# CCD.net
KiCad netlist of a schematic drawn in Altium Designer
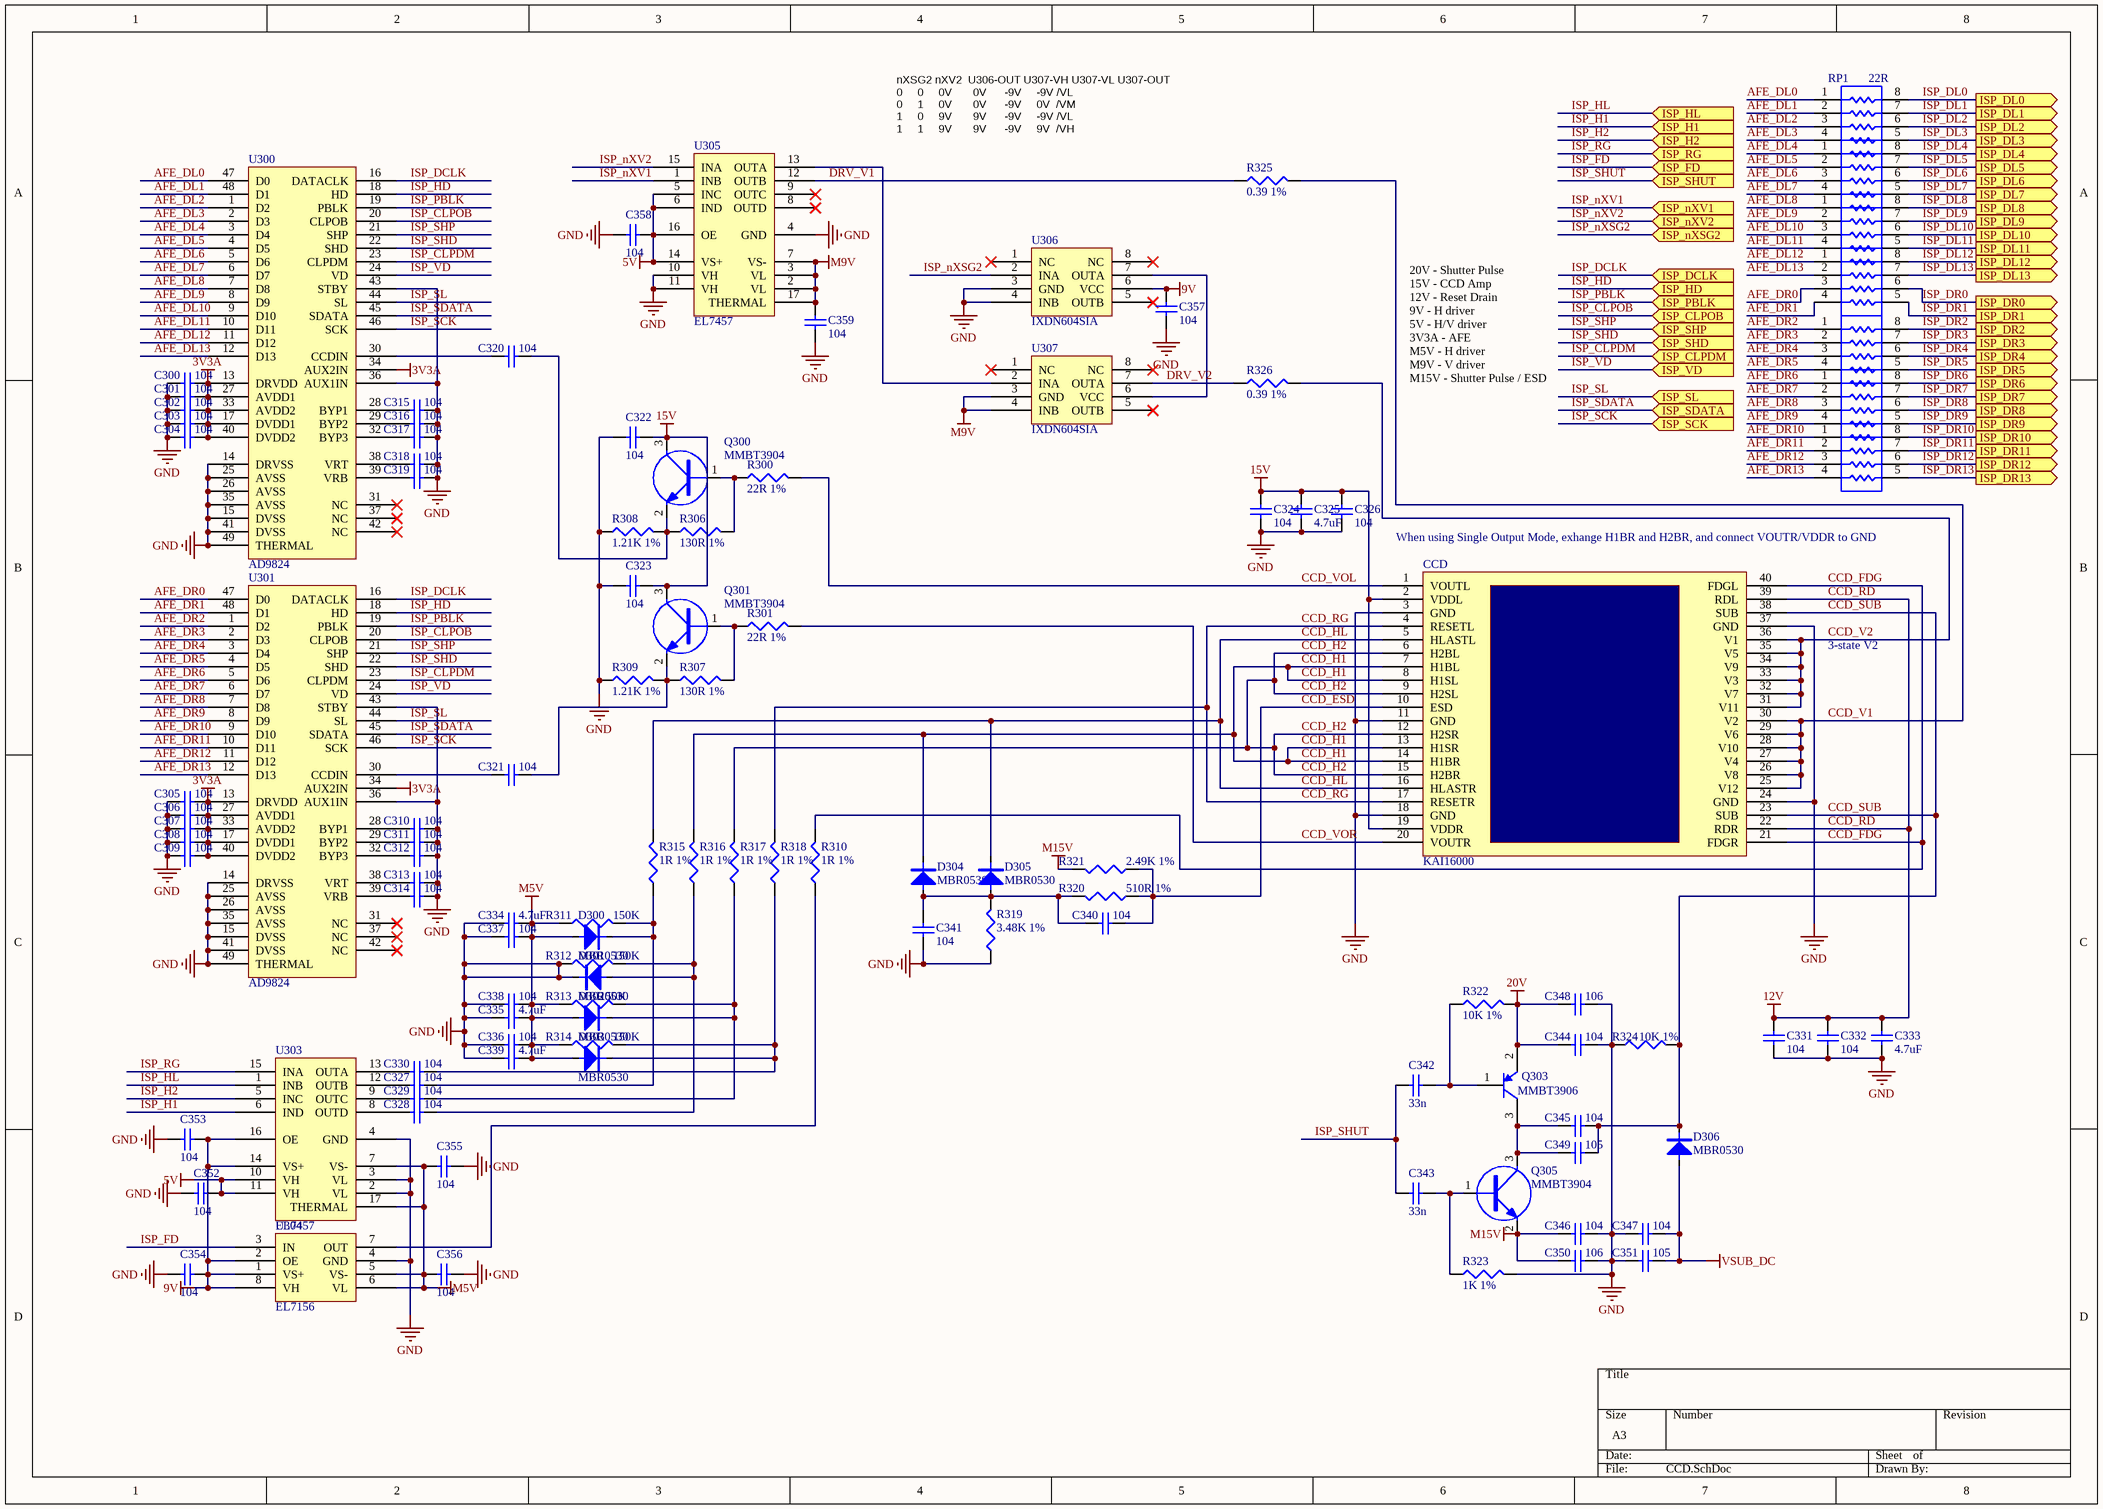
[diagram p0: CCD.SchDoc]

(export (version "E")
  (design (tool "Eeschema 10.0.6"))
  (components
    (comp (ref "C300")
      (value "104")
      (footprint "C0402")
      (description "Capacitor (Semiconductor SIM Model)")
      (fields (field (name "PUBLISHER") "Altium Limited"))
      (libsource (lib "Miscellaneous Devices") (part "Cap Semi"))
    )
    (comp (ref "C301")
      (value "104")
      (footprint "C0402")
      (description "Capacitor (Semiconductor SIM Model)")
      (fields (field (name "PUBLISHER") "Altium Limited"))
      (libsource (lib "Miscellaneous Devices") (part "Cap Semi"))
    )
    (comp (ref "C302")
      (value "104")
      (footprint "C0402")
      (description "Capacitor (Semiconductor SIM Model)")
      (fields (field (name "PUBLISHER") "Altium Limited"))
      (libsource (lib "Miscellaneous Devices") (part "Cap Semi"))
    )
    (comp (ref "C303")
      (value "104")
      (footprint "C0402")
      (description "Capacitor (Semiconductor SIM Model)")
      (fields (field (name "PUBLISHER") "Altium Limited"))
      (libsource (lib "Miscellaneous Devices") (part "Cap Semi"))
    )
    (comp (ref "C304")
      (value "104")
      (footprint "C0402")
      (description "Capacitor (Semiconductor SIM Model)")
      (fields (field (name "PUBLISHER") "Altium Limited"))
      (libsource (lib "Miscellaneous Devices") (part "Cap Semi"))
    )
    (comp (ref "C305")
      (value "104")
      (footprint "C0402")
      (description "Capacitor (Semiconductor SIM Model)")
      (fields (field (name "PUBLISHER") "Altium Limited"))
      (libsource (lib "Miscellaneous Devices") (part "Cap Semi"))
    )
    (comp (ref "C306")
      (value "104")
      (footprint "C0402")
      (description "Capacitor (Semiconductor SIM Model)")
      (fields (field (name "PUBLISHER") "Altium Limited"))
      (libsource (lib "Miscellaneous Devices") (part "Cap Semi"))
    )
    (comp (ref "C307")
      (value "104")
      (footprint "C0402")
      (description "Capacitor (Semiconductor SIM Model)")
      (fields (field (name "PUBLISHER") "Altium Limited"))
      (libsource (lib "Miscellaneous Devices") (part "Cap Semi"))
    )
    (comp (ref "C308")
      (value "104")
      (footprint "C0402")
      (description "Capacitor (Semiconductor SIM Model)")
      (fields (field (name "PUBLISHER") "Altium Limited"))
      (libsource (lib "Miscellaneous Devices") (part "Cap Semi"))
    )
    (comp (ref "C309")
      (value "104")
      (footprint "C0402")
      (description "Capacitor (Semiconductor SIM Model)")
      (fields (field (name "PUBLISHER") "Altium Limited"))
      (libsource (lib "Miscellaneous Devices") (part "Cap Semi"))
    )
    (comp (ref "C310")
      (value "104")
      (footprint "C0402")
      (description "Capacitor (Semiconductor SIM Model)")
      (fields (field (name "PUBLISHER") "Altium Limited"))
      (libsource (lib "Miscellaneous Devices") (part "Cap Semi"))
    )
    (comp (ref "C311")
      (value "104")
      (footprint "C0402")
      (description "Capacitor (Semiconductor SIM Model)")
      (fields (field (name "PUBLISHER") "Altium Limited"))
      (libsource (lib "Miscellaneous Devices") (part "Cap Semi"))
    )
    (comp (ref "C312")
      (value "104")
      (footprint "C0402")
      (description "Capacitor (Semiconductor SIM Model)")
      (fields (field (name "PUBLISHER") "Altium Limited"))
      (libsource (lib "Miscellaneous Devices") (part "Cap Semi"))
    )
    (comp (ref "C313")
      (value "104")
      (footprint "C0402")
      (description "Capacitor (Semiconductor SIM Model)")
      (fields (field (name "PUBLISHER") "Altium Limited"))
      (libsource (lib "Miscellaneous Devices") (part "Cap Semi"))
    )
    (comp (ref "C314")
      (value "104")
      (footprint "C0402")
      (description "Capacitor (Semiconductor SIM Model)")
      (fields (field (name "PUBLISHER") "Altium Limited"))
      (libsource (lib "Miscellaneous Devices") (part "Cap Semi"))
    )
    (comp (ref "C315")
      (value "104")
      (footprint "C0402")
      (description "Capacitor (Semiconductor SIM Model)")
      (fields (field (name "PUBLISHER") "Altium Limited"))
      (libsource (lib "Miscellaneous Devices") (part "Cap Semi"))
    )
    (comp (ref "C316")
      (value "104")
      (footprint "C0402")
      (description "Capacitor (Semiconductor SIM Model)")
      (fields (field (name "PUBLISHER") "Altium Limited"))
      (libsource (lib "Miscellaneous Devices") (part "Cap Semi"))
    )
    (comp (ref "C317")
      (value "104")
      (footprint "C0402")
      (description "Capacitor (Semiconductor SIM Model)")
      (fields (field (name "PUBLISHER") "Altium Limited"))
      (libsource (lib "Miscellaneous Devices") (part "Cap Semi"))
    )
    (comp (ref "C318")
      (value "104")
      (footprint "C0402")
      (description "Capacitor (Semiconductor SIM Model)")
      (fields (field (name "PUBLISHER") "Altium Limited"))
      (libsource (lib "Miscellaneous Devices") (part "Cap Semi"))
    )
    (comp (ref "C319")
      (value "104")
      (footprint "C0402")
      (description "Capacitor (Semiconductor SIM Model)")
      (fields (field (name "PUBLISHER") "Altium Limited"))
      (libsource (lib "Miscellaneous Devices") (part "Cap Semi"))
    )
    (comp (ref "C320")
      (value "104")
      (footprint "C0402")
      (description "Capacitor (Semiconductor SIM Model)")
      (fields (field (name "PUBLISHER") "Altium Limited"))
      (libsource (lib "Miscellaneous Devices") (part "Cap Semi"))
    )
    (comp (ref "C321")
      (value "104")
      (footprint "C0402")
      (description "Capacitor (Semiconductor SIM Model)")
      (fields (field (name "PUBLISHER") "Altium Limited"))
      (libsource (lib "Miscellaneous Devices") (part "Cap Semi"))
    )
    (comp (ref "C322")
      (value "104")
      (footprint "C0402")
      (description "Capacitor (Semiconductor SIM Model)")
      (fields (field (name "PUBLISHER") "Altium Limited"))
      (libsource (lib "Miscellaneous Devices") (part "Cap Semi"))
    )
    (comp (ref "C323")
      (value "104")
      (footprint "C0402")
      (description "Capacitor (Semiconductor SIM Model)")
      (fields (field (name "PUBLISHER") "Altium Limited"))
      (libsource (lib "Miscellaneous Devices") (part "Cap Semi"))
    )
    (comp (ref "C324")
      (value "104")
      (footprint "C0402")
      (description "Capacitor (Semiconductor SIM Model)")
      (fields (field (name "PUBLISHER") "Altium Limited"))
      (libsource (lib "Miscellaneous Devices") (part "Cap Semi"))
    )
    (comp (ref "C325")
      (value "4.7uF")
      (footprint "C0603")
      (description "Capacitor (Semiconductor SIM Model)")
      (fields (field (name "PUBLISHER") "Altium Limited"))
      (libsource (lib "Miscellaneous Devices") (part "Cap Semi"))
    )
    (comp (ref "C326")
      (value "104")
      (footprint "C0402")
      (description "Capacitor (Semiconductor SIM Model)")
      (fields (field (name "PUBLISHER") "Altium Limited"))
      (libsource (lib "Miscellaneous Devices") (part "Cap Semi"))
    )
    (comp (ref "C327")
      (value "104")
      (footprint "C0402")
      (description "Capacitor (Semiconductor SIM Model)")
      (fields (field (name "PUBLISHER") "Altium Limited"))
      (libsource (lib "Miscellaneous Devices") (part "Cap Semi"))
    )
    (comp (ref "C328")
      (value "104")
      (footprint "C0402")
      (description "Capacitor (Semiconductor SIM Model)")
      (fields (field (name "PUBLISHER") "Altium Limited"))
      (libsource (lib "Miscellaneous Devices") (part "Cap Semi"))
    )
    (comp (ref "C329")
      (value "104")
      (footprint "C0402")
      (description "Capacitor (Semiconductor SIM Model)")
      (fields (field (name "PUBLISHER") "Altium Limited"))
      (libsource (lib "Miscellaneous Devices") (part "Cap Semi"))
    )
    (comp (ref "C330")
      (value "104")
      (footprint "C0402")
      (description "Capacitor (Semiconductor SIM Model)")
      (fields (field (name "PUBLISHER") "Altium Limited"))
      (libsource (lib "Miscellaneous Devices") (part "Cap Semi"))
    )
    (comp (ref "C331")
      (value "104")
      (footprint "C0402")
      (description "Capacitor (Semiconductor SIM Model)")
      (fields (field (name "PUBLISHER") "Altium Limited"))
      (libsource (lib "Miscellaneous Devices") (part "Cap Semi"))
    )
    (comp (ref "C332")
      (value "104")
      (footprint "C0402")
      (description "Capacitor (Semiconductor SIM Model)")
      (fields (field (name "PUBLISHER") "Altium Limited"))
      (libsource (lib "Miscellaneous Devices") (part "Cap Semi"))
    )
    (comp (ref "C333")
      (value "4.7uF")
      (footprint "C0603")
      (description "Capacitor (Semiconductor SIM Model)")
      (fields (field (name "PUBLISHER") "Altium Limited"))
      (libsource (lib "Miscellaneous Devices") (part "Cap Semi"))
    )
    (comp (ref "C334")
      (value "104")
      (footprint "C0603")
      (description "Capacitor (Semiconductor SIM Model)")
      (fields (field (name "PUBLISHER") "Altium Limited"))
      (libsource (lib "Miscellaneous Devices") (part "Cap Semi"))
    )
    (comp (ref "C335")
      (value "4.7uF")
      (footprint "C0603")
      (description "Capacitor (Semiconductor SIM Model)")
      (fields (field (name "PUBLISHER") "Altium Limited"))
      (libsource (lib "Miscellaneous Devices") (part "Cap Semi"))
    )
    (comp (ref "C336")
      (value "104")
      (footprint "C0603")
      (description "Capacitor (Semiconductor SIM Model)")
      (fields (field (name "PUBLISHER") "Altium Limited"))
      (libsource (lib "Miscellaneous Devices") (part "Cap Semi"))
    )
    (comp (ref "C337")
      (value "4.7uF")
      (footprint "C0603")
      (description "Capacitor (Semiconductor SIM Model)")
      (fields (field (name "PUBLISHER") "Altium Limited"))
      (libsource (lib "Miscellaneous Devices") (part "Cap Semi"))
    )
    (comp (ref "C338")
      (value "104")
      (footprint "C0603")
      (description "Capacitor (Semiconductor SIM Model)")
      (fields (field (name "PUBLISHER") "Altium Limited"))
      (libsource (lib "Miscellaneous Devices") (part "Cap Semi"))
    )
    (comp (ref "C339")
      (value "4.7uF")
      (footprint "C0603")
      (description "Capacitor (Semiconductor SIM Model)")
      (fields (field (name "PUBLISHER") "Altium Limited"))
      (libsource (lib "Miscellaneous Devices") (part "Cap Semi"))
    )
    (comp (ref "C340")
      (value "104")
      (footprint "C0603")
      (description "Capacitor (Semiconductor SIM Model)")
      (fields (field (name "PUBLISHER") "Altium Limited"))
      (libsource (lib "Miscellaneous Devices") (part "Cap Semi"))
    )
    (comp (ref "C341")
      (value "104")
      (footprint "C0603")
      (description "Capacitor (Semiconductor SIM Model)")
      (fields (field (name "PUBLISHER") "Altium Limited"))
      (libsource (lib "Miscellaneous Devices") (part "Cap Semi"))
    )
    (comp (ref "C342")
      (value "33n")
      (footprint "C0402")
      (description "Capacitor (Semiconductor SIM Model)")
      (fields (field (name "PUBLISHER") "Altium Limited"))
      (libsource (lib "Miscellaneous Devices") (part "Cap Semi"))
    )
    (comp (ref "C343")
      (value "33n")
      (footprint "C0402")
      (description "Capacitor (Semiconductor SIM Model)")
      (fields (field (name "PUBLISHER") "Altium Limited"))
      (libsource (lib "Miscellaneous Devices") (part "Cap Semi"))
    )
    (comp (ref "C344")
      (value "104")
      (footprint "C0402")
      (description "Capacitor (Semiconductor SIM Model)")
      (fields (field (name "PUBLISHER") "Altium Limited"))
      (libsource (lib "Miscellaneous Devices") (part "Cap Semi"))
    )
    (comp (ref "C345")
      (value "104")
      (footprint "C0402")
      (description "Capacitor (Semiconductor SIM Model)")
      (fields (field (name "PUBLISHER") "Altium Limited"))
      (libsource (lib "Miscellaneous Devices") (part "Cap Semi"))
    )
    (comp (ref "C346")
      (value "104")
      (footprint "C0402")
      (description "Capacitor (Semiconductor SIM Model)")
      (fields (field (name "PUBLISHER") "Altium Limited"))
      (libsource (lib "Miscellaneous Devices") (part "Cap Semi"))
    )
    (comp (ref "C347")
      (value "104")
      (footprint "C0402")
      (description "Capacitor (Semiconductor SIM Model)")
      (fields (field (name "PUBLISHER") "Altium Limited"))
      (libsource (lib "Miscellaneous Devices") (part "Cap Semi"))
    )
    (comp (ref "C348")
      (value "106")
      (footprint "C0805")
      (description "Capacitor (Semiconductor SIM Model)")
      (fields (field (name "PUBLISHER") "Altium Limited"))
      (libsource (lib "Miscellaneous Devices") (part "Cap Semi"))
    )
    (comp (ref "C349")
      (value "105")
      (footprint "C0805")
      (description "Capacitor (Semiconductor SIM Model)")
      (fields (field (name "PUBLISHER") "Altium Limited"))
      (libsource (lib "Miscellaneous Devices") (part "Cap Semi"))
    )
    (comp (ref "C350")
      (value "106")
      (footprint "C0805")
      (description "Capacitor (Semiconductor SIM Model)")
      (fields (field (name "PUBLISHER") "Altium Limited"))
      (libsource (lib "Miscellaneous Devices") (part "Cap Semi"))
    )
    (comp (ref "C351")
      (value "105")
      (footprint "C0805")
      (description "Capacitor (Semiconductor SIM Model)")
      (fields (field (name "PUBLISHER") "Altium Limited"))
      (libsource (lib "Miscellaneous Devices") (part "Cap Semi"))
    )
    (comp (ref "C352")
      (value "104")
      (description "Capacitor (Semiconductor SIM Model)")
      (fields (field (name "PUBLISHER") "Altium Limited"))
      (libsource (lib "Miscellaneous Devices") (part "Cap Semi"))
    )
    (comp (ref "C353")
      (value "104")
      (description "Capacitor (Semiconductor SIM Model)")
      (fields (field (name "PUBLISHER") "Altium Limited"))
      (libsource (lib "Miscellaneous Devices") (part "Cap Semi"))
    )
    (comp (ref "C354")
      (value "104")
      (description "Capacitor (Semiconductor SIM Model)")
      (fields (field (name "PUBLISHER") "Altium Limited"))
      (libsource (lib "Miscellaneous Devices") (part "Cap Semi"))
    )
    (comp (ref "C355")
      (value "104")
      (description "Capacitor (Semiconductor SIM Model)")
      (fields (field (name "PUBLISHER") "Altium Limited"))
      (libsource (lib "Miscellaneous Devices") (part "Cap Semi"))
    )
    (comp (ref "C356")
      (value "104")
      (description "Capacitor (Semiconductor SIM Model)")
      (fields (field (name "PUBLISHER") "Altium Limited"))
      (libsource (lib "Miscellaneous Devices") (part "Cap Semi"))
    )
    (comp (ref "C357")
      (value "104")
      (description "Capacitor (Semiconductor SIM Model)")
      (fields (field (name "PUBLISHER") "Altium Limited"))
      (libsource (lib "Miscellaneous Devices") (part "Cap Semi"))
    )
    (comp (ref "C358")
      (value "104")
      (description "Capacitor (Semiconductor SIM Model)")
      (fields (field (name "PUBLISHER") "Altium Limited"))
      (libsource (lib "Miscellaneous Devices") (part "Cap Semi"))
    )
    (comp (ref "C359")
      (value "104")
      (description "Capacitor (Semiconductor SIM Model)")
      (fields (field (name "PUBLISHER") "Altium Limited"))
      (libsource (lib "Miscellaneous Devices") (part "Cap Semi"))
    )
    (comp (ref "CCD") (value "KAI16000") (footprint "KAI16000") (libsource (lib "Schlib1") (part "KAI16000")))
    (comp (ref "D300") (value "MBR0530") (footprint "SOD123") (libsource (lib "Schlib1") (part "MBR0530")))
    (comp (ref "D301") (value "MBR0530") (footprint "SOD123") (libsource (lib "Schlib1") (part "MBR0530")))
    (comp (ref "D302") (value "MBR0530") (footprint "SOD123") (libsource (lib "Schlib1") (part "MBR0530")))
    (comp (ref "D303") (value "MBR0530") (footprint "SOD123") (libsource (lib "Schlib1") (part "MBR0530")))
    (comp (ref "D304") (value "MBR0530") (footprint "SOD123") (libsource (lib "Schlib1") (part "MBR0530")))
    (comp (ref "D305") (value "MBR0530") (footprint "SOD123") (libsource (lib "Schlib1") (part "MBR0530")))
    (comp (ref "D306") (value "MBR0530") (footprint "SOD123") (libsource (lib "Schlib1") (part "MBR0530")))
    (comp (ref "Q300") (value "MMBT3904") (footprint "SOT23") (libsource (lib "Schlib1") (part "MMBT3904")))
    (comp (ref "Q301") (value "MMBT3904") (footprint "SOT23") (libsource (lib "Schlib1") (part "MMBT3904")))
    (comp (ref "Q303")
      (value "MMBT3906")
      (footprint "SOT23")
      (fields (field (name "PUBLISHER") "Altium Limited"))
      (libsource (lib "Schlib1") (part "MMBT3906"))
    )
    (comp (ref "Q305") (value "MMBT3904") (footprint "SOT23") (libsource (lib "Schlib1") (part "MMBT3904")))
    (comp (ref "R300")
      (value "22R 1%")
      (footprint "R0603")
      (description "Resistor")
      (fields (field (name "PUBLISHER") "Altium Limited"))
      (libsource (lib "Miscellaneous Devices") (part "Res3"))
    )
    (comp (ref "R301")
      (value "22R 1%")
      (footprint "R0603")
      (description "Resistor")
      (fields (field (name "PUBLISHER") "Altium Limited"))
      (libsource (lib "Miscellaneous Devices") (part "Res3"))
    )
    (comp (ref "R306")
      (value "130R 1%")
      (footprint "R0603")
      (description "Resistor")
      (fields (field (name "PUBLISHER") "Altium Limited"))
      (libsource (lib "Miscellaneous Devices") (part "Res3"))
    )
    (comp (ref "R307")
      (value "130R 1%")
      (footprint "R0603")
      (description "Resistor")
      (fields (field (name "PUBLISHER") "Altium Limited"))
      (libsource (lib "Miscellaneous Devices") (part "Res3"))
    )
    (comp (ref "R308")
      (value "1.21K 1%")
      (footprint "R0603")
      (description "Resistor")
      (fields (field (name "PUBLISHER") "Altium Limited"))
      (libsource (lib "Miscellaneous Devices") (part "Res3"))
    )
    (comp (ref "R309")
      (value "1.21K 1%")
      (footprint "R0603")
      (description "Resistor")
      (fields (field (name "PUBLISHER") "Altium Limited"))
      (libsource (lib "Miscellaneous Devices") (part "Res3"))
    )
    (comp (ref "R310")
      (value "1R 1%")
      (footprint "R0805")
      (description "Resistor")
      (fields (field (name "PUBLISHER") "Altium Limited"))
      (libsource (lib "Miscellaneous Devices") (part "Res3"))
    )
    (comp (ref "R311")
      (value "150K")
      (footprint "R0603")
      (description "Resistor")
      (fields (field (name "PUBLISHER") "Altium Limited"))
      (libsource (lib "Miscellaneous Devices") (part "Res3"))
    )
    (comp (ref "R312")
      (value "150K")
      (footprint "R0603")
      (description "Resistor")
      (fields (field (name "PUBLISHER") "Altium Limited"))
      (libsource (lib "Miscellaneous Devices") (part "Res3"))
    )
    (comp (ref "R313")
      (value "150K")
      (footprint "R0603")
      (description "Resistor")
      (fields (field (name "PUBLISHER") "Altium Limited"))
      (libsource (lib "Miscellaneous Devices") (part "Res3"))
    )
    (comp (ref "R314")
      (value "150K")
      (footprint "R0603")
      (description "Resistor")
      (fields (field (name "PUBLISHER") "Altium Limited"))
      (libsource (lib "Miscellaneous Devices") (part "Res3"))
    )
    (comp (ref "R315")
      (value "1R 1%")
      (footprint "R0805")
      (description "Resistor")
      (fields (field (name "PUBLISHER") "Altium Limited"))
      (libsource (lib "Miscellaneous Devices") (part "Res3"))
    )
    (comp (ref "R316")
      (value "1R 1%")
      (footprint "R0805")
      (description "Resistor")
      (fields (field (name "PUBLISHER") "Altium Limited"))
      (libsource (lib "Miscellaneous Devices") (part "Res3"))
    )
    (comp (ref "R317")
      (value "1R 1%")
      (footprint "R0805")
      (description "Resistor")
      (fields (field (name "PUBLISHER") "Altium Limited"))
      (libsource (lib "Miscellaneous Devices") (part "Res3"))
    )
    (comp (ref "R318")
      (value "1R 1%")
      (footprint "R0805")
      (description "Resistor")
      (fields (field (name "PUBLISHER") "Altium Limited"))
      (libsource (lib "Miscellaneous Devices") (part "Res3"))
    )
    (comp (ref "R319")
      (value "3.48K 1%")
      (footprint "R0603")
      (description "Resistor")
      (fields (field (name "PUBLISHER") "Altium Limited"))
      (libsource (lib "Miscellaneous Devices") (part "Res3"))
    )
    (comp (ref "R320")
      (value "510R 1%")
      (footprint "R0603")
      (description "Resistor")
      (fields (field (name "PUBLISHER") "Altium Limited"))
      (libsource (lib "Miscellaneous Devices") (part "Res3"))
    )
    (comp (ref "R321")
      (value "2.49K 1%")
      (footprint "R0603")
      (description "Resistor")
      (fields (field (name "PUBLISHER") "Altium Limited"))
      (libsource (lib "Miscellaneous Devices") (part "Res3"))
    )
    (comp (ref "R322")
      (value "10K 1%")
      (footprint "R0603")
      (description "Resistor")
      (fields (field (name "PUBLISHER") "Altium Limited"))
      (libsource (lib "Miscellaneous Devices") (part "Res3"))
    )
    (comp (ref "R323")
      (value "1K 1%")
      (footprint "R0603")
      (description "Resistor")
      (fields (field (name "PUBLISHER") "Altium Limited"))
      (libsource (lib "Miscellaneous Devices") (part "Res3"))
    )
    (comp (ref "R324")
      (value "10K 1%")
      (footprint "R0603")
      (description "Resistor")
      (fields (field (name "PUBLISHER") "Altium Limited"))
      (libsource (lib "Miscellaneous Devices") (part "Res3"))
    )
    (comp (ref "R325")
      (value "0.39 1%")
      (footprint "R0603")
      (description "Resistor")
      (fields (field (name "PUBLISHER") "Altium Limited"))
      (libsource (lib "Miscellaneous Devices") (part "Res3"))
    )
    (comp (ref "R326")
      (value "0.39 1%")
      (footprint "R0603")
      (description "Resistor")
      (fields (field (name "PUBLISHER") "Altium Limited"))
      (libsource (lib "Miscellaneous Devices") (part "Res3"))
    )
    (comp (ref "RP1")
      (value "22R")
      (footprint "R0402S4")
      (description "Isolated Resistor Network")
      (fields (field (name "PUBLISHER") "Altium Limited"))
      (libsource (lib "Schlib1") (part "ResPack"))
    )
    (comp (ref "RP2")
      (value "22R")
      (footprint "R0402S4")
      (description "Isolated Resistor Network")
      (fields (field (name "PUBLISHER") "Altium Limited"))
      (libsource (lib "Schlib1") (part "ResPack"))
    )
    (comp (ref "RP3")
      (value "22R")
      (footprint "R0402S4")
      (description "Isolated Resistor Network")
      (fields (field (name "PUBLISHER") "Altium Limited"))
      (libsource (lib "Schlib1") (part "ResPack"))
    )
    (comp (ref "RP4")
      (value "22R")
      (footprint "R0402S4")
      (description "Isolated Resistor Network")
      (fields (field (name "PUBLISHER") "Altium Limited"))
      (libsource (lib "Schlib1") (part "ResPack"))
    )
    (comp (ref "RP5")
      (value "22R")
      (footprint "R0402S4")
      (description "Isolated Resistor Network")
      (fields (field (name "PUBLISHER") "Altium Limited"))
      (libsource (lib "Schlib1") (part "ResPack"))
    )
    (comp (ref "RP6")
      (value "22R")
      (footprint "R0402S4")
      (description "Isolated Resistor Network")
      (fields (field (name "PUBLISHER") "Altium Limited"))
      (libsource (lib "Schlib1") (part "ResPack"))
    )
    (comp (ref "RP7")
      (value "22R")
      (footprint "R0402S4")
      (description "Isolated Resistor Network")
      (fields (field (name "PUBLISHER") "Altium Limited"))
      (libsource (lib "Schlib1") (part "ResPack"))
    )
    (comp (ref "U300") (value "AD9824") (footprint "CP-48") (libsource (lib "Schlib1") (part "AD9824")))
    (comp (ref "U301") (value "AD9824") (footprint "CP-48") (libsource (lib "Schlib1") (part "AD9824")))
    (comp (ref "U303") (value "EL7457") (footprint "QFN16") (libsource (lib "Schlib1") (part "EL7457")))
    (comp (ref "U304") (value "EL7156") (footprint "SOP-8") (libsource (lib "Schlib1") (part "EL7156")))
    (comp (ref "U305") (value "EL7457") (footprint "QFN16") (libsource (lib "Schlib1") (part "EL7457")))
    (comp (ref "U306")
      (value "IXDN604SIA")
      (footprint "SOP8")
      (libsource (lib "Schlib1") (part "IXDN604SIA"))
    )
    (comp (ref "U307")
      (value "IXDN604SIA")
      (footprint "SOP8")
      (libsource (lib "Schlib1") (part "IXDN604SIA"))
    )
  )
  (nets
    (net (code "1") (name "/AFE_DL0") (class "Default")
      (node (ref "RP1") (pin "1") (pinfunction "1_1") (pintype "passive"))
      (node (ref "U300") (pin "47") (pinfunction "D0_47") (pintype "passive"))
    )
    (net (code "2") (name "/AFE_DL1") (class "Default")
      (node (ref "RP1") (pin "2") (pinfunction "2_2") (pintype "passive"))
      (node (ref "U300") (pin "48") (pinfunction "D1_48") (pintype "passive"))
    )
    (net (code "3") (name "/AFE_DL2") (class "Default")
      (node (ref "RP1") (pin "3") (pinfunction "3_3") (pintype "passive"))
      (node (ref "U300") (pin "1") (pinfunction "D2_1") (pintype "passive"))
    )
    (net (code "4") (name "/AFE_DL3") (class "Default")
      (node (ref "RP1") (pin "4") (pinfunction "4_4") (pintype "passive"))
      (node (ref "U300") (pin "2") (pinfunction "D3_2") (pintype "passive"))
    )
    (net (code "5") (name "/AFE_DL4") (class "Default")
      (node (ref "RP2") (pin "1") (pinfunction "1_1") (pintype "passive"))
      (node (ref "U300") (pin "3") (pinfunction "D4_3") (pintype "passive"))
    )
    (net (code "6") (name "/AFE_DL5") (class "Default")
      (node (ref "RP2") (pin "2") (pinfunction "2_2") (pintype "passive"))
      (node (ref "U300") (pin "4") (pinfunction "D5_4") (pintype "passive"))
    )
    (net (code "7") (name "/AFE_DL6") (class "Default")
      (node (ref "RP2") (pin "3") (pinfunction "3_3") (pintype "passive"))
      (node (ref "U300") (pin "5") (pinfunction "D6_5") (pintype "passive"))
    )
    (net (code "8") (name "/AFE_DL7") (class "Default")
      (node (ref "RP2") (pin "4") (pinfunction "4_4") (pintype "passive"))
      (node (ref "U300") (pin "6") (pinfunction "D7_6") (pintype "passive"))
    )
    (net (code "9") (name "/AFE_DL8") (class "Default")
      (node (ref "RP3") (pin "1") (pinfunction "1_1") (pintype "passive"))
      (node (ref "U300") (pin "7") (pinfunction "D8_7") (pintype "passive"))
    )
    (net (code "10") (name "/AFE_DL9") (class "Default")
      (node (ref "RP3") (pin "2") (pinfunction "2_2") (pintype "passive"))
      (node (ref "U300") (pin "8") (pinfunction "D9_8") (pintype "passive"))
    )
    (net (code "11") (name "/AFE_DL10") (class "Default")
      (node (ref "RP3") (pin "3") (pinfunction "3_3") (pintype "passive"))
      (node (ref "U300") (pin "9") (pinfunction "D10_9") (pintype "passive"))
    )
    (net (code "12") (name "/AFE_DL11") (class "Default")
      (node (ref "RP3") (pin "4") (pinfunction "4_4") (pintype "passive"))
      (node (ref "U300") (pin "10") (pinfunction "D11_10") (pintype "passive"))
    )
    (net (code "13") (name "/AFE_DL12") (class "Default")
      (node (ref "RP4") (pin "1") (pinfunction "1_1") (pintype "passive"))
      (node (ref "U300") (pin "11") (pinfunction "D12_11") (pintype "passive"))
    )
    (net (code "14") (name "/AFE_DL13") (class "Default")
      (node (ref "RP4") (pin "2") (pinfunction "2_2") (pintype "passive"))
      (node (ref "U300") (pin "12") (pinfunction "D13_12") (pintype "passive"))
    )
    (net (code "15") (name "/AFE_DR0") (class "Default")
      (node (ref "RP4") (pin "3") (pinfunction "3_3") (pintype "passive"))
      (node (ref "U301") (pin "47") (pinfunction "D0_47") (pintype "passive"))
    )
    (net (code "16") (name "/AFE_DR1") (class "Default")
      (node (ref "RP4") (pin "4") (pinfunction "4_4") (pintype "passive"))
      (node (ref "U301") (pin "48") (pinfunction "D1_48") (pintype "passive"))
    )
    (net (code "17") (name "/AFE_DR2") (class "Default")
      (node (ref "RP5") (pin "1") (pinfunction "1_1") (pintype "passive"))
      (node (ref "U301") (pin "1") (pinfunction "D2_1") (pintype "passive"))
    )
    (net (code "18") (name "/AFE_DR3") (class "Default")
      (node (ref "RP5") (pin "2") (pinfunction "2_2") (pintype "passive"))
      (node (ref "U301") (pin "2") (pinfunction "D3_2") (pintype "passive"))
    )
    (net (code "19") (name "/AFE_DR4") (class "Default")
      (node (ref "RP5") (pin "3") (pinfunction "3_3") (pintype "passive"))
      (node (ref "U301") (pin "3") (pinfunction "D4_3") (pintype "passive"))
    )
    (net (code "20") (name "/AFE_DR5") (class "Default")
      (node (ref "RP5") (pin "4") (pinfunction "4_4") (pintype "passive"))
      (node (ref "U301") (pin "4") (pinfunction "D5_4") (pintype "passive"))
    )
    (net (code "21") (name "/AFE_DR6") (class "Default")
      (node (ref "RP7") (pin "1") (pinfunction "1_1") (pintype "passive"))
      (node (ref "U301") (pin "5") (pinfunction "D6_5") (pintype "passive"))
    )
    (net (code "22") (name "/AFE_DR7") (class "Default")
      (node (ref "RP7") (pin "2") (pinfunction "2_2") (pintype "passive"))
      (node (ref "U301") (pin "6") (pinfunction "D7_6") (pintype "passive"))
    )
    (net (code "23") (name "/AFE_DR8") (class "Default")
      (node (ref "RP7") (pin "3") (pinfunction "3_3") (pintype "passive"))
      (node (ref "U301") (pin "7") (pinfunction "D8_7") (pintype "passive"))
    )
    (net (code "24") (name "/AFE_DR9") (class "Default")
      (node (ref "RP7") (pin "4") (pinfunction "4_4") (pintype "passive"))
      (node (ref "U301") (pin "8") (pinfunction "D9_8") (pintype "passive"))
    )
    (net (code "25") (name "/AFE_DR10") (class "Default")
      (node (ref "RP6") (pin "1") (pinfunction "1_1") (pintype "passive"))
      (node (ref "U301") (pin "9") (pinfunction "D10_9") (pintype "passive"))
    )
    (net (code "26") (name "/AFE_DR11") (class "Default")
      (node (ref "RP6") (pin "2") (pinfunction "2_2") (pintype "passive"))
      (node (ref "U301") (pin "10") (pinfunction "D11_10") (pintype "passive"))
    )
    (net (code "27") (name "/AFE_DR12") (class "Default")
      (node (ref "RP6") (pin "3") (pinfunction "3_3") (pintype "passive"))
      (node (ref "U301") (pin "11") (pinfunction "D12_11") (pintype "passive"))
    )
    (net (code "28") (name "/AFE_DR13") (class "Default")
      (node (ref "RP6") (pin "4") (pinfunction "4_4") (pintype "passive"))
      (node (ref "U301") (pin "12") (pinfunction "D13_12") (pintype "passive"))
    )
    (net (code "29") (name "/CCD_ESD") (class "Default")
      (node (ref "C340") (pin "2") (pinfunction "2_2") (pintype "passive"))
      (node (ref "CCD") (pin "10") (pinfunction "ESD_10") (pintype "passive"))
      (node (ref "R320") (pin "1") (pinfunction "1_1") (pintype "passive"))
      (node (ref "R321") (pin "1") (pinfunction "1_1") (pintype "passive"))
    )
    (net (code "30") (name "/CCD_FDG") (class "Default")
      (node (ref "CCD") (pin "21") (pinfunction "FDGR_21") (pintype "passive"))
      (node (ref "CCD") (pin "40") (pinfunction "FDGL_40") (pintype "passive"))
      (node (ref "R310") (pin "2") (pinfunction "2_2") (pintype "passive"))
    )
    (net (code "31") (name "/CCD_H1") (class "Default")
      (node (ref "CCD") (pin "13") (pinfunction "H1SR_13") (pintype "passive"))
      (node (ref "CCD") (pin "14") (pinfunction "H1BR_14") (pintype "passive"))
      (node (ref "CCD") (pin "7") (pinfunction "H1BL_7") (pintype "passive"))
      (node (ref "CCD") (pin "8") (pinfunction "H1SL_8") (pintype "passive"))
      (node (ref "D304") (pin "2") (pinfunction "2_2") (pintype "passive"))
      (node (ref "R316") (pin "2") (pinfunction "2_2") (pintype "passive"))
    )
    (net (code "32") (name "/CCD_H2") (class "Default")
      (node (ref "CCD") (pin "12") (pinfunction "H2SR_12") (pintype "passive"))
      (node (ref "CCD") (pin "15") (pinfunction "H2BR_15") (pintype "passive"))
      (node (ref "CCD") (pin "6") (pinfunction "H2BL_6") (pintype "passive"))
      (node (ref "CCD") (pin "9") (pinfunction "H2SL_9") (pintype "passive"))
      (node (ref "R317") (pin "2") (pinfunction "2_2") (pintype "passive"))
    )
    (net (code "33") (name "/CCD_HL") (class "Default")
      (node (ref "CCD") (pin "16") (pinfunction "HLASTR_16") (pintype "passive"))
      (node (ref "CCD") (pin "5") (pinfunction "HLASTL_5") (pintype "passive"))
      (node (ref "D305") (pin "2") (pinfunction "2_2") (pintype "passive"))
      (node (ref "R315") (pin "2") (pinfunction "2_2") (pintype "passive"))
    )
    (net (code "34") (name "/CCD_RG") (class "Default")
      (node (ref "CCD") (pin "17") (pinfunction "RESETR_17") (pintype "passive"))
      (node (ref "CCD") (pin "4") (pinfunction "RESETL_4") (pintype "passive"))
      (node (ref "R318") (pin "2") (pinfunction "2_2") (pintype "passive"))
    )
    (net (code "35") (name "/CCD_SUB") (class "Default")
      (node (ref "C345") (pin "2") (pinfunction "2_2") (pintype "passive"))
      (node (ref "C349") (pin "2") (pinfunction "2_2") (pintype "passive"))
      (node (ref "CCD") (pin "23") (pinfunction "SUB_23") (pintype "passive"))
      (node (ref "CCD") (pin "38") (pinfunction "SUB_38") (pintype "passive"))
      (node (ref "D306") (pin "2") (pinfunction "2_2") (pintype "passive"))
      (node (ref "R324") (pin "2") (pinfunction "2_2") (pintype "passive"))
    )
    (net (code "36") (name "/CCD_V1") (class "Default")
      (node (ref "CCD") (pin "25") (pinfunction "V12_25") (pintype "passive"))
      (node (ref "CCD") (pin "26") (pinfunction "V8_26") (pintype "passive"))
      (node (ref "CCD") (pin "27") (pinfunction "V4_27") (pintype "passive"))
      (node (ref "CCD") (pin "28") (pinfunction "V10_28") (pintype "passive"))
      (node (ref "CCD") (pin "29") (pinfunction "V6_29") (pintype "passive"))
      (node (ref "CCD") (pin "30") (pinfunction "V2_30") (pintype "passive"))
      (node (ref "R325") (pin "2") (pinfunction "2_2") (pintype "passive"))
    )
    (net (code "37") (name "/CCD_V2") (class "Default")
      (node (ref "CCD") (pin "31") (pinfunction "V11_31") (pintype "passive"))
      (node (ref "CCD") (pin "32") (pinfunction "V7_32") (pintype "passive"))
      (node (ref "CCD") (pin "33") (pinfunction "V3_33") (pintype "passive"))
      (node (ref "CCD") (pin "34") (pinfunction "V9_34") (pintype "passive"))
      (node (ref "CCD") (pin "35") (pinfunction "V5_35") (pintype "passive"))
      (node (ref "CCD") (pin "36") (pinfunction "V1_36") (pintype "passive"))
      (node (ref "R326") (pin "2") (pinfunction "2_2") (pintype "passive"))
    )
    (net (code "38") (name "/CCD_VOL") (class "Default")
      (node (ref "CCD") (pin "1") (pinfunction "VOUTL_1") (pintype "passive"))
      (node (ref "R300") (pin "2") (pinfunction "2_2") (pintype "passive"))
    )
    (net (code "39") (name "/CCD_VOR") (class "Default")
      (node (ref "CCD") (pin "20") (pinfunction "VOUTR_20") (pintype "passive"))
      (node (ref "R301") (pin "2") (pinfunction "2_2") (pintype "passive"))
    )
    (net (code "40") (name "/DRV_V1") (class "Default")
      (node (ref "R325") (pin "1") (pinfunction "1_1") (pintype "passive"))
      (node (ref "U305") (pin "12") (pinfunction "OUTB_12") (pintype "passive"))
    )
    (net (code "41") (name "/DRV_V2") (class "Default")
      (node (ref "R326") (pin "1") (pinfunction "1_1") (pintype "passive"))
      (node (ref "U307") (pin "7") (pinfunction "OUTA_7") (pintype "passive"))
    )
    (net (code "42") (name "/ISP_CLPDM") (class "Default")
      (node (ref "U300") (pin "23") (pinfunction "CLPDM_23") (pintype "passive"))
      (node (ref "U301") (pin "23") (pinfunction "CLPDM_23") (pintype "passive"))
    )
    (net (code "43") (name "/ISP_CLPOB") (class "Default")
      (node (ref "U300") (pin "20") (pinfunction "CLPOB_20") (pintype "passive"))
      (node (ref "U301") (pin "20") (pinfunction "CLPOB_20") (pintype "passive"))
    )
    (net (code "44") (name "/ISP_DCLK") (class "Default")
      (node (ref "U300") (pin "16") (pinfunction "DATACLK_16") (pintype "passive"))
      (node (ref "U301") (pin "16") (pinfunction "DATACLK_16") (pintype "passive"))
    )
    (net (code "45") (name "/ISP_DL0") (class "Default")
      (node (ref "RP1") (pin "8") (pinfunction "8_8") (pintype "passive"))
    )
    (net (code "46") (name "/ISP_DL1") (class "Default")
      (node (ref "RP1") (pin "7") (pinfunction "7_7") (pintype "passive"))
    )
    (net (code "47") (name "/ISP_DL2") (class "Default")
      (node (ref "RP1") (pin "6") (pinfunction "6_6") (pintype "passive"))
    )
    (net (code "48") (name "/ISP_DL3") (class "Default")
      (node (ref "RP1") (pin "5") (pinfunction "5_5") (pintype "passive"))
    )
    (net (code "49") (name "/ISP_DL4") (class "Default")
      (node (ref "RP2") (pin "8") (pinfunction "8_8") (pintype "passive"))
    )
    (net (code "50") (name "/ISP_DL5") (class "Default")
      (node (ref "RP2") (pin "7") (pinfunction "7_7") (pintype "passive"))
    )
    (net (code "51") (name "/ISP_DL6") (class "Default")
      (node (ref "RP2") (pin "6") (pinfunction "6_6") (pintype "passive"))
    )
    (net (code "52") (name "/ISP_DL7") (class "Default")
      (node (ref "RP2") (pin "5") (pinfunction "5_5") (pintype "passive"))
    )
    (net (code "53") (name "/ISP_DL8") (class "Default")
      (node (ref "RP3") (pin "8") (pinfunction "8_8") (pintype "passive"))
    )
    (net (code "54") (name "/ISP_DL9") (class "Default")
      (node (ref "RP3") (pin "7") (pinfunction "7_7") (pintype "passive"))
    )
    (net (code "55") (name "/ISP_DL10") (class "Default")
      (node (ref "RP3") (pin "6") (pinfunction "6_6") (pintype "passive"))
    )
    (net (code "56") (name "/ISP_DL11") (class "Default")
      (node (ref "RP3") (pin "5") (pinfunction "5_5") (pintype "passive"))
    )
    (net (code "57") (name "/ISP_DL12") (class "Default")
      (node (ref "RP4") (pin "8") (pinfunction "8_8") (pintype "passive"))
    )
    (net (code "58") (name "/ISP_DL13") (class "Default")
      (node (ref "RP4") (pin "7") (pinfunction "7_7") (pintype "passive"))
    )
    (net (code "59") (name "/ISP_DR0") (class "Default")
      (node (ref "RP4") (pin "6") (pinfunction "6_6") (pintype "passive"))
    )
    (net (code "60") (name "/ISP_DR1") (class "Default")
      (node (ref "RP4") (pin "5") (pinfunction "5_5") (pintype "passive"))
    )
    (net (code "61") (name "/ISP_DR2") (class "Default")
      (node (ref "RP5") (pin "8") (pinfunction "8_8") (pintype "passive"))
    )
    (net (code "62") (name "/ISP_DR3") (class "Default")
      (node (ref "RP5") (pin "7") (pinfunction "7_7") (pintype "passive"))
    )
    (net (code "63") (name "/ISP_DR4") (class "Default")
      (node (ref "RP5") (pin "6") (pinfunction "6_6") (pintype "passive"))
    )
    (net (code "64") (name "/ISP_DR5") (class "Default")
      (node (ref "RP5") (pin "5") (pinfunction "5_5") (pintype "passive"))
    )
    (net (code "65") (name "/ISP_DR6") (class "Default")
      (node (ref "RP7") (pin "8") (pinfunction "8_8") (pintype "passive"))
    )
    (net (code "66") (name "/ISP_DR7") (class "Default")
      (node (ref "RP7") (pin "7") (pinfunction "7_7") (pintype "passive"))
    )
    (net (code "67") (name "/ISP_DR8") (class "Default")
      (node (ref "RP7") (pin "6") (pinfunction "6_6") (pintype "passive"))
    )
    (net (code "68") (name "/ISP_DR9") (class "Default")
      (node (ref "RP7") (pin "5") (pinfunction "5_5") (pintype "passive"))
    )
    (net (code "69") (name "/ISP_DR10") (class "Default")
      (node (ref "RP6") (pin "8") (pinfunction "8_8") (pintype "passive"))
    )
    (net (code "70") (name "/ISP_DR11") (class "Default")
      (node (ref "RP6") (pin "7") (pinfunction "7_7") (pintype "passive"))
    )
    (net (code "71") (name "/ISP_DR12") (class "Default")
      (node (ref "RP6") (pin "6") (pinfunction "6_6") (pintype "passive"))
    )
    (net (code "72") (name "/ISP_DR13") (class "Default")
      (node (ref "RP6") (pin "5") (pinfunction "5_5") (pintype "passive"))
    )
    (net (code "73") (name "/ISP_FD") (class "Default")
      (node (ref "U304") (pin "3") (pinfunction "IN_3") (pintype "passive"))
    )
    (net (code "74") (name "/ISP_H1") (class "Default")
      (node (ref "U303") (pin "6") (pinfunction "IND_6") (pintype "passive"))
    )
    (net (code "75") (name "/ISP_H2") (class "Default")
      (node (ref "U303") (pin "5") (pinfunction "INC_5") (pintype "passive"))
    )
    (net (code "76") (name "/ISP_HD") (class "Default")
      (node (ref "U300") (pin "18") (pinfunction "HD_18") (pintype "passive"))
      (node (ref "U301") (pin "18") (pinfunction "HD_18") (pintype "passive"))
    )
    (net (code "77") (name "/ISP_HL") (class "Default")
      (node (ref "U303") (pin "1") (pinfunction "INB_1") (pintype "passive"))
    )
    (net (code "78") (name "/ISP_PBLK") (class "Default")
      (node (ref "U300") (pin "19") (pinfunction "PBLK_19") (pintype "passive"))
      (node (ref "U301") (pin "19") (pinfunction "PBLK_19") (pintype "passive"))
    )
    (net (code "79") (name "/ISP_RG") (class "Default")
      (node (ref "U303") (pin "15") (pinfunction "INA_15") (pintype "passive"))
    )
    (net (code "80") (name "/ISP_SCK") (class "Default")
      (node (ref "U300") (pin "46") (pinfunction "SCK_46") (pintype "passive"))
      (node (ref "U301") (pin "46") (pinfunction "SCK_46") (pintype "passive"))
    )
    (net (code "81") (name "/ISP_SDATA") (class "Default")
      (node (ref "U300") (pin "45") (pinfunction "SDATA_45") (pintype "passive"))
      (node (ref "U301") (pin "45") (pinfunction "SDATA_45") (pintype "passive"))
    )
    (net (code "82") (name "/ISP_SHD") (class "Default")
      (node (ref "U300") (pin "22") (pinfunction "SHD_22") (pintype "passive"))
      (node (ref "U301") (pin "22") (pinfunction "SHD_22") (pintype "passive"))
    )
    (net (code "83") (name "/ISP_SHP") (class "Default")
      (node (ref "U300") (pin "21") (pinfunction "SHP_21") (pintype "passive"))
      (node (ref "U301") (pin "21") (pinfunction "SHP_21") (pintype "passive"))
    )
    (net (code "84") (name "/ISP_SHUT") (class "Default")
      (node (ref "C342") (pin "1") (pinfunction "1_1") (pintype "passive"))
      (node (ref "C343") (pin "1") (pinfunction "1_1") (pintype "passive"))
    )
    (net (code "85") (name "/ISP_SL") (class "Default")
      (node (ref "U300") (pin "44") (pinfunction "SL_44") (pintype "passive"))
      (node (ref "U301") (pin "44") (pinfunction "SL_44") (pintype "passive"))
    )
    (net (code "86") (name "/ISP_VD") (class "Default")
      (node (ref "U300") (pin "24") (pinfunction "VD_24") (pintype "passive"))
      (node (ref "U301") (pin "24") (pinfunction "VD_24") (pintype "passive"))
    )
    (net (code "87") (name "/ISP_nXSG2") (class "Default")
      (node (ref "U306") (pin "2") (pinfunction "INA_2") (pintype "passive"))
    )
    (net (code "88") (name "/ISP_nXV1") (class "Default")
      (node (ref "U305") (pin "1") (pinfunction "INB_1") (pintype "passive"))
    )
    (net (code "89") (name "/ISP_nXV2") (class "Default")
      (node (ref "U305") (pin "15") (pinfunction "INA_15") (pintype "passive"))
    )
    (net (code "90") (name "3V3A") (class "Default")
      (node (ref "C300") (pin "2") (pinfunction "2_2") (pintype "passive"))
      (node (ref "C301") (pin "2") (pinfunction "2_2") (pintype "passive"))
      (node (ref "C302") (pin "2") (pinfunction "2_2") (pintype "passive"))
      (node (ref "C303") (pin "2") (pinfunction "2_2") (pintype "passive"))
      (node (ref "C304") (pin "2") (pinfunction "2_2") (pintype "passive"))
      (node (ref "C305") (pin "2") (pinfunction "2_2") (pintype "passive"))
      (node (ref "C306") (pin "2") (pinfunction "2_2") (pintype "passive"))
      (node (ref "C307") (pin "2") (pinfunction "2_2") (pintype "passive"))
      (node (ref "C308") (pin "2") (pinfunction "2_2") (pintype "passive"))
      (node (ref "C309") (pin "2") (pinfunction "2_2") (pintype "passive"))
      (node (ref "U300") (pin "13") (pinfunction "DRVDD_13") (pintype "passive"))
      (node (ref "U300") (pin "17") (pinfunction "DVDD1_17") (pintype "passive"))
      (node (ref "U300") (pin "27") (pinfunction "AVDD1_27") (pintype "passive"))
      (node (ref "U300") (pin "33") (pinfunction "AVDD2_33") (pintype "passive"))
      (node (ref "U300") (pin "34") (pinfunction "AUX2IN_34") (pintype "passive"))
      (node (ref "U300") (pin "40") (pinfunction "DVDD2_40") (pintype "passive"))
      (node (ref "U301") (pin "13") (pinfunction "DRVDD_13") (pintype "passive"))
      (node (ref "U301") (pin "17") (pinfunction "DVDD1_17") (pintype "passive"))
      (node (ref "U301") (pin "27") (pinfunction "AVDD1_27") (pintype "passive"))
      (node (ref "U301") (pin "33") (pinfunction "AVDD2_33") (pintype "passive"))
      (node (ref "U301") (pin "34") (pinfunction "AUX2IN_34") (pintype "passive"))
      (node (ref "U301") (pin "40") (pinfunction "DVDD2_40") (pintype "passive"))
    )
    (net (code "91") (name "5V") (class "Default")
      (node (ref "C352") (pin "2") (pinfunction "2_2") (pintype "passive"))
      (node (ref "C358") (pin "2") (pinfunction "2_2") (pintype "passive"))
      (node (ref "U303") (pin "10") (pinfunction "VH_10") (pintype "passive"))
      (node (ref "U303") (pin "11") (pinfunction "VH_11") (pintype "passive"))
      (node (ref "U305") (pin "14") (pinfunction "VS+_14") (pintype "passive"))
      (node (ref "U305") (pin "16") (pinfunction "OE_16") (pintype "passive"))
      (node (ref "U305") (pin "5") (pinfunction "INC_5") (pintype "passive"))
      (node (ref "U305") (pin "6") (pinfunction "IND_6") (pintype "passive"))
    )
    (net (code "92") (name "9V") (class "Default")
      (node (ref "C353") (pin "1") (pinfunction "1_1") (pintype "passive"))
      (node (ref "C354") (pin "1") (pinfunction "1_1") (pintype "passive"))
      (node (ref "C357") (pin "1") (pinfunction "1_1") (pintype "passive"))
      (node (ref "U303") (pin "14") (pinfunction "VS+_14") (pintype "passive"))
      (node (ref "U303") (pin "16") (pinfunction "OE_16") (pintype "passive"))
      (node (ref "U304") (pin "1") (pinfunction "VS+_1") (pintype "passive"))
      (node (ref "U304") (pin "2") (pinfunction "OE_2") (pintype "passive"))
      (node (ref "U304") (pin "8") (pinfunction "VH_8") (pintype "passive"))
      (node (ref "U306") (pin "6") (pinfunction "VCC_6") (pintype "passive"))
    )
    (net (code "93") (name "12V") (class "Default")
      (node (ref "C331") (pin "2") (pinfunction "2_2") (pintype "passive"))
      (node (ref "C332") (pin "2") (pinfunction "2_2") (pintype "passive"))
      (node (ref "C333") (pin "2") (pinfunction "2_2") (pintype "passive"))
      (node (ref "CCD") (pin "22") (pinfunction "RDR_22") (pintype "passive"))
      (node (ref "CCD") (pin "39") (pinfunction "RDL_39") (pintype "passive"))
    )
    (net (code "94") (name "15V") (class "Default")
      (node (ref "C322") (pin "2") (pinfunction "2_2") (pintype "passive"))
      (node (ref "C323") (pin "2") (pinfunction "2_2") (pintype "passive"))
      (node (ref "C324") (pin "2") (pinfunction "2_2") (pintype "passive"))
      (node (ref "C325") (pin "2") (pinfunction "2_2") (pintype "passive"))
      (node (ref "C326") (pin "2") (pinfunction "2_2") (pintype "passive"))
      (node (ref "CCD") (pin "19") (pinfunction "VDDR_19") (pintype "passive"))
      (node (ref "CCD") (pin "2") (pinfunction "VDDL_2") (pintype "passive"))
      (node (ref "Q300") (pin "3") (pinfunction "C_3") (pintype "passive"))
      (node (ref "Q301") (pin "3") (pinfunction "C_3") (pintype "passive"))
    )
    (net (code "95") (name "20V") (class "Default")
      (node (ref "C344") (pin "1") (pinfunction "1_1") (pintype "passive"))
      (node (ref "C348") (pin "1") (pinfunction "1_1") (pintype "passive"))
      (node (ref "Q303") (pin "2") (pinfunction "E_2") (pintype "passive"))
      (node (ref "R322") (pin "2") (pinfunction "2_2") (pintype "passive"))
    )
    (net (code "96") (name "GND") (class "Default")
      (node (ref "C300") (pin "1") (pinfunction "1_1") (pintype "passive"))
      (node (ref "C301") (pin "1") (pinfunction "1_1") (pintype "passive"))
      (node (ref "C302") (pin "1") (pinfunction "1_1") (pintype "passive"))
      (node (ref "C303") (pin "1") (pinfunction "1_1") (pintype "passive"))
      (node (ref "C304") (pin "1") (pinfunction "1_1") (pintype "passive"))
      (node (ref "C305") (pin "1") (pinfunction "1_1") (pintype "passive"))
      (node (ref "C306") (pin "1") (pinfunction "1_1") (pintype "passive"))
      (node (ref "C307") (pin "1") (pinfunction "1_1") (pintype "passive"))
      (node (ref "C308") (pin "1") (pinfunction "1_1") (pintype "passive"))
      (node (ref "C309") (pin "1") (pinfunction "1_1") (pintype "passive"))
      (node (ref "C310") (pin "2") (pinfunction "2_2") (pintype "passive"))
      (node (ref "C311") (pin "2") (pinfunction "2_2") (pintype "passive"))
      (node (ref "C312") (pin "2") (pinfunction "2_2") (pintype "passive"))
      (node (ref "C313") (pin "2") (pinfunction "2_2") (pintype "passive"))
      (node (ref "C314") (pin "2") (pinfunction "2_2") (pintype "passive"))
      (node (ref "C315") (pin "2") (pinfunction "2_2") (pintype "passive"))
      (node (ref "C316") (pin "2") (pinfunction "2_2") (pintype "passive"))
      (node (ref "C317") (pin "2") (pinfunction "2_2") (pintype "passive"))
      (node (ref "C318") (pin "2") (pinfunction "2_2") (pintype "passive"))
      (node (ref "C319") (pin "2") (pinfunction "2_2") (pintype "passive"))
      (node (ref "C322") (pin "1") (pinfunction "1_1") (pintype "passive"))
      (node (ref "C323") (pin "1") (pinfunction "1_1") (pintype "passive"))
      (node (ref "C324") (pin "1") (pinfunction "1_1") (pintype "passive"))
      (node (ref "C325") (pin "1") (pinfunction "1_1") (pintype "passive"))
      (node (ref "C326") (pin "1") (pinfunction "1_1") (pintype "passive"))
      (node (ref "C331") (pin "1") (pinfunction "1_1") (pintype "passive"))
      (node (ref "C332") (pin "1") (pinfunction "1_1") (pintype "passive"))
      (node (ref "C333") (pin "1") (pinfunction "1_1") (pintype "passive"))
      (node (ref "C334") (pin "1") (pinfunction "1_1") (pintype "passive"))
      (node (ref "C335") (pin "1") (pinfunction "1_1") (pintype "passive"))
      (node (ref "C336") (pin "1") (pinfunction "1_1") (pintype "passive"))
      (node (ref "C337") (pin "1") (pinfunction "1_1") (pintype "passive"))
      (node (ref "C338") (pin "1") (pinfunction "1_1") (pintype "passive"))
      (node (ref "C339") (pin "1") (pinfunction "1_1") (pintype "passive"))
      (node (ref "C341") (pin "1") (pinfunction "1_1") (pintype "passive"))
      (node (ref "C344") (pin "2") (pinfunction "2_2") (pintype "passive"))
      (node (ref "C346") (pin "2") (pinfunction "2_2") (pintype "passive"))
      (node (ref "C347") (pin "1") (pinfunction "1_1") (pintype "passive"))
      (node (ref "C348") (pin "2") (pinfunction "2_2") (pintype "passive"))
      (node (ref "C350") (pin "2") (pinfunction "2_2") (pintype "passive"))
      (node (ref "C351") (pin "1") (pinfunction "1_1") (pintype "passive"))
      (node (ref "C352") (pin "1") (pinfunction "1_1") (pintype "passive"))
      (node (ref "C353") (pin "2") (pinfunction "2_2") (pintype "passive"))
      (node (ref "C354") (pin "2") (pinfunction "2_2") (pintype "passive"))
      (node (ref "C355") (pin "1") (pinfunction "1_1") (pintype "passive"))
      (node (ref "C356") (pin "1") (pinfunction "1_1") (pintype "passive"))
      (node (ref "C357") (pin "2") (pinfunction "2_2") (pintype "passive"))
      (node (ref "C358") (pin "1") (pinfunction "1_1") (pintype "passive"))
      (node (ref "C359") (pin "1") (pinfunction "1_1") (pintype "passive"))
      (node (ref "CCD") (pin "11") (pinfunction "GND_11") (pintype "passive"))
      (node (ref "CCD") (pin "18") (pinfunction "GND_18") (pintype "passive"))
      (node (ref "CCD") (pin "24") (pinfunction "GND_24") (pintype "passive"))
      (node (ref "CCD") (pin "3") (pinfunction "GND_3") (pintype "passive"))
      (node (ref "CCD") (pin "37") (pinfunction "GND_37") (pintype "passive"))
      (node (ref "D301") (pin "2") (pinfunction "2_2") (pintype "passive"))
      (node (ref "R308") (pin "1") (pinfunction "1_1") (pintype "passive"))
      (node (ref "R309") (pin "1") (pinfunction "1_1") (pintype "passive"))
      (node (ref "R312") (pin "1") (pinfunction "1_1") (pintype "passive"))
      (node (ref "R319") (pin "1") (pinfunction "1_1") (pintype "passive"))
      (node (ref "R323") (pin "2") (pinfunction "2_2") (pintype "passive"))
      (node (ref "R324") (pin "1") (pinfunction "1_1") (pintype "passive"))
      (node (ref "U300") (pin "14") (pinfunction "DRVSS_14") (pintype "passive"))
      (node (ref "U300") (pin "15") (pinfunction "DVSS_15") (pintype "passive"))
      (node (ref "U300") (pin "25") (pinfunction "AVSS_25") (pintype "passive"))
      (node (ref "U300") (pin "26") (pinfunction "AVSS_26") (pintype "passive"))
      (node (ref "U300") (pin "35") (pinfunction "AVSS_35") (pintype "passive"))
      (node (ref "U300") (pin "36") (pinfunction "AUX1IN_36") (pintype "passive"))
      (node (ref "U300") (pin "41") (pinfunction "DVSS_41") (pintype "passive"))
      (node (ref "U300") (pin "43") (pinfunction "STBY_43") (pintype "passive"))
      (node (ref "U300") (pin "49") (pinfunction "THERMAL_49") (pintype "passive"))
      (node (ref "U301") (pin "14") (pinfunction "DRVSS_14") (pintype "passive"))
      (node (ref "U301") (pin "15") (pinfunction "DVSS_15") (pintype "passive"))
      (node (ref "U301") (pin "25") (pinfunction "AVSS_25") (pintype "passive"))
      (node (ref "U301") (pin "26") (pinfunction "AVSS_26") (pintype "passive"))
      (node (ref "U301") (pin "35") (pinfunction "AVSS_35") (pintype "passive"))
      (node (ref "U301") (pin "36") (pinfunction "AUX1IN_36") (pintype "passive"))
      (node (ref "U301") (pin "41") (pinfunction "DVSS_41") (pintype "passive"))
      (node (ref "U301") (pin "43") (pinfunction "STBY_43") (pintype "passive"))
      (node (ref "U301") (pin "49") (pinfunction "THERMAL_49") (pintype "passive"))
      (node (ref "U303") (pin "2") (pinfunction "VL_2") (pintype "passive"))
      (node (ref "U303") (pin "3") (pinfunction "VL_3") (pintype "passive"))
      (node (ref "U303") (pin "4") (pinfunction "GND_4") (pintype "passive"))
      (node (ref "U304") (pin "4") (pinfunction "GND_4") (pintype "passive"))
      (node (ref "U305") (pin "10") (pinfunction "VH_10") (pintype "passive"))
      (node (ref "U305") (pin "11") (pinfunction "VH_11") (pintype "passive"))
      (node (ref "U305") (pin "4") (pinfunction "GND_4") (pintype "passive"))
      (node (ref "U306") (pin "3") (pinfunction "GND_3") (pintype "passive"))
      (node (ref "U306") (pin "4") (pinfunction "INB_4") (pintype "passive"))
    )
    (net (code "97") (name "M5V") (class "Default")
      (node (ref "C334") (pin "2") (pinfunction "2_2") (pintype "passive"))
      (node (ref "C335") (pin "2") (pinfunction "2_2") (pintype "passive"))
      (node (ref "C336") (pin "2") (pinfunction "2_2") (pintype "passive"))
      (node (ref "C337") (pin "2") (pinfunction "2_2") (pintype "passive"))
      (node (ref "C338") (pin "2") (pinfunction "2_2") (pintype "passive"))
      (node (ref "C339") (pin "2") (pinfunction "2_2") (pintype "passive"))
      (node (ref "C355") (pin "2") (pinfunction "2_2") (pintype "passive"))
      (node (ref "C356") (pin "2") (pinfunction "2_2") (pintype "passive"))
      (node (ref "D300") (pin "1") (pinfunction "1_1") (pintype "passive"))
      (node (ref "D302") (pin "1") (pinfunction "1_1") (pintype "passive"))
      (node (ref "D303") (pin "1") (pinfunction "1_1") (pintype "passive"))
      (node (ref "R311") (pin "1") (pinfunction "1_1") (pintype "passive"))
      (node (ref "R313") (pin "1") (pinfunction "1_1") (pintype "passive"))
      (node (ref "R314") (pin "1") (pinfunction "1_1") (pintype "passive"))
      (node (ref "U303") (pin "17") (pinfunction "THERMAL_17") (pintype "passive"))
      (node (ref "U303") (pin "7") (pinfunction "VS-_7") (pintype "passive"))
      (node (ref "U304") (pin "5") (pinfunction "VS-_5") (pintype "passive"))
      (node (ref "U304") (pin "6") (pinfunction "VL_6") (pintype "passive"))
    )
    (net (code "98") (name "M9V") (class "Default")
      (node (ref "C359") (pin "2") (pinfunction "2_2") (pintype "passive"))
      (node (ref "U305") (pin "17") (pinfunction "THERMAL_17") (pintype "passive"))
      (node (ref "U305") (pin "2") (pinfunction "VL_2") (pintype "passive"))
      (node (ref "U305") (pin "3") (pinfunction "VL_3") (pintype "passive"))
      (node (ref "U305") (pin "7") (pinfunction "VS-_7") (pintype "passive"))
      (node (ref "U307") (pin "3") (pinfunction "GND_3") (pintype "passive"))
      (node (ref "U307") (pin "4") (pinfunction "INB_4") (pintype "passive"))
    )
    (net (code "99") (name "M15V") (class "Default")
      (node (ref "C346") (pin "1") (pinfunction "1_1") (pintype "passive"))
      (node (ref "C350") (pin "1") (pinfunction "1_1") (pintype "passive"))
      (node (ref "Q305") (pin "2") (pinfunction "E_2") (pintype "passive"))
      (node (ref "R321") (pin "2") (pinfunction "2_2") (pintype "passive"))
    )
    (net (code "100") (name "Net-(C327-Pad2)") (class "Default")
      (node (ref "C327") (pin "2") (pinfunction "2_2") (pintype "passive"))
      (node (ref "D300") (pin "2") (pinfunction "2_2") (pintype "passive"))
      (node (ref "R311") (pin "2") (pinfunction "2_2") (pintype "passive"))
      (node (ref "R315") (pin "1") (pinfunction "1_1") (pintype "passive"))
    )
    (net (code "101") (name "Net-(C328-Pad2)") (class "Default")
      (node (ref "C328") (pin "2") (pinfunction "2_2") (pintype "passive"))
      (node (ref "D301") (pin "1") (pinfunction "1_1") (pintype "passive"))
      (node (ref "R312") (pin "2") (pinfunction "2_2") (pintype "passive"))
      (node (ref "R316") (pin "1") (pinfunction "1_1") (pintype "passive"))
    )
    (net (code "102") (name "Net-(C329-Pad2)") (class "Default")
      (node (ref "C329") (pin "2") (pinfunction "2_2") (pintype "passive"))
      (node (ref "D302") (pin "2") (pinfunction "2_2") (pintype "passive"))
      (node (ref "R313") (pin "2") (pinfunction "2_2") (pintype "passive"))
      (node (ref "R317") (pin "1") (pinfunction "1_1") (pintype "passive"))
    )
    (net (code "103") (name "Net-(C330-Pad2)") (class "Default")
      (node (ref "C330") (pin "2") (pinfunction "2_2") (pintype "passive"))
      (node (ref "D303") (pin "2") (pinfunction "2_2") (pintype "passive"))
      (node (ref "R314") (pin "2") (pinfunction "2_2") (pintype "passive"))
      (node (ref "R318") (pin "1") (pinfunction "1_1") (pintype "passive"))
    )
    (net (code "104") (name "Net-(C340-Pad1)") (class "Default")
      (node (ref "C340") (pin "1") (pinfunction "1_1") (pintype "passive"))
      (node (ref "C341") (pin "2") (pinfunction "2_2") (pintype "passive"))
      (node (ref "D304") (pin "1") (pinfunction "1_1") (pintype "passive"))
      (node (ref "D305") (pin "1") (pinfunction "1_1") (pintype "passive"))
      (node (ref "R319") (pin "2") (pinfunction "2_2") (pintype "passive"))
      (node (ref "R320") (pin "2") (pinfunction "2_2") (pintype "passive"))
    )
    (net (code "105") (name "Net-(Q300-B)") (class "Default")
      (node (ref "Q300") (pin "1") (pinfunction "B_1") (pintype "passive"))
      (node (ref "R300") (pin "1") (pinfunction "1_1") (pintype "passive"))
      (node (ref "R306") (pin "2") (pinfunction "2_2") (pintype "passive"))
    )
    (net (code "106") (name "Net-(Q300-E)") (class "Default")
      (node (ref "C320") (pin "2") (pinfunction "2_2") (pintype "passive"))
      (node (ref "Q300") (pin "2") (pinfunction "E_2") (pintype "passive"))
      (node (ref "R306") (pin "1") (pinfunction "1_1") (pintype "passive"))
      (node (ref "R308") (pin "2") (pinfunction "2_2") (pintype "passive"))
    )
    (net (code "107") (name "Net-(Q301-B)") (class "Default")
      (node (ref "Q301") (pin "1") (pinfunction "B_1") (pintype "passive"))
      (node (ref "R301") (pin "1") (pinfunction "1_1") (pintype "passive"))
      (node (ref "R307") (pin "2") (pinfunction "2_2") (pintype "passive"))
    )
    (net (code "108") (name "Net-(Q301-E)") (class "Default")
      (node (ref "C321") (pin "2") (pinfunction "2_2") (pintype "passive"))
      (node (ref "Q301") (pin "2") (pinfunction "E_2") (pintype "passive"))
      (node (ref "R307") (pin "1") (pinfunction "1_1") (pintype "passive"))
      (node (ref "R309") (pin "2") (pinfunction "2_2") (pintype "passive"))
    )
    (net (code "109") (name "Net-(Q303-B)") (class "Default")
      (node (ref "C342") (pin "2") (pinfunction "2_2") (pintype "passive"))
      (node (ref "Q303") (pin "1") (pinfunction "B_1") (pintype "passive"))
      (node (ref "R322") (pin "1") (pinfunction "1_1") (pintype "passive"))
    )
    (net (code "110") (name "Net-(Q303-C)") (class "Default")
      (node (ref "C345") (pin "1") (pinfunction "1_1") (pintype "passive"))
      (node (ref "C349") (pin "1") (pinfunction "1_1") (pintype "passive"))
      (node (ref "Q303") (pin "3") (pinfunction "C_3") (pintype "passive"))
      (node (ref "Q305") (pin "3") (pinfunction "C_3") (pintype "passive"))
    )
    (net (code "111") (name "Net-(Q305-B)") (class "Default")
      (node (ref "C343") (pin "2") (pinfunction "2_2") (pintype "passive"))
      (node (ref "Q305") (pin "1") (pinfunction "B_1") (pintype "passive"))
      (node (ref "R323") (pin "1") (pinfunction "1_1") (pintype "passive"))
    )
    (net (code "112") (name "Net-(U300-BYP1)") (class "Default")
      (node (ref "C315") (pin "1") (pinfunction "1_1") (pintype "passive"))
      (node (ref "U300") (pin "28") (pinfunction "BYP1_28") (pintype "passive"))
    )
    (net (code "113") (name "Net-(U300-BYP2)") (class "Default")
      (node (ref "C316") (pin "1") (pinfunction "1_1") (pintype "passive"))
      (node (ref "U300") (pin "29") (pinfunction "BYP2_29") (pintype "passive"))
    )
    (net (code "114") (name "Net-(U300-BYP3)") (class "Default")
      (node (ref "C317") (pin "1") (pinfunction "1_1") (pintype "passive"))
      (node (ref "U300") (pin "32") (pinfunction "BYP3_32") (pintype "passive"))
    )
    (net (code "115") (name "Net-(U300-CCDIN)") (class "Default")
      (node (ref "C320") (pin "1") (pinfunction "1_1") (pintype "passive"))
      (node (ref "U300") (pin "30") (pinfunction "CCDIN_30") (pintype "passive"))
    )
    (net (code "116") (name "Net-(U300-VRB)") (class "Default")
      (node (ref "C319") (pin "1") (pinfunction "1_1") (pintype "passive"))
      (node (ref "U300") (pin "39") (pinfunction "VRB_39") (pintype "passive"))
    )
    (net (code "117") (name "Net-(U300-VRT)") (class "Default")
      (node (ref "C318") (pin "1") (pinfunction "1_1") (pintype "passive"))
      (node (ref "U300") (pin "38") (pinfunction "VRT_38") (pintype "passive"))
    )
    (net (code "118") (name "Net-(U301-BYP1)") (class "Default")
      (node (ref "C310") (pin "1") (pinfunction "1_1") (pintype "passive"))
      (node (ref "U301") (pin "28") (pinfunction "BYP1_28") (pintype "passive"))
    )
    (net (code "119") (name "Net-(U301-BYP2)") (class "Default")
      (node (ref "C311") (pin "1") (pinfunction "1_1") (pintype "passive"))
      (node (ref "U301") (pin "29") (pinfunction "BYP2_29") (pintype "passive"))
    )
    (net (code "120") (name "Net-(U301-BYP3)") (class "Default")
      (node (ref "C312") (pin "1") (pinfunction "1_1") (pintype "passive"))
      (node (ref "U301") (pin "32") (pinfunction "BYP3_32") (pintype "passive"))
    )
    (net (code "121") (name "Net-(U301-CCDIN)") (class "Default")
      (node (ref "C321") (pin "1") (pinfunction "1_1") (pintype "passive"))
      (node (ref "U301") (pin "30") (pinfunction "CCDIN_30") (pintype "passive"))
    )
    (net (code "122") (name "Net-(U301-VRB)") (class "Default")
      (node (ref "C314") (pin "1") (pinfunction "1_1") (pintype "passive"))
      (node (ref "U301") (pin "39") (pinfunction "VRB_39") (pintype "passive"))
    )
    (net (code "123") (name "Net-(U301-VRT)") (class "Default")
      (node (ref "C313") (pin "1") (pinfunction "1_1") (pintype "passive"))
      (node (ref "U301") (pin "38") (pinfunction "VRT_38") (pintype "passive"))
    )
    (net (code "124") (name "Net-(U303-OUTA)") (class "Default")
      (node (ref "C330") (pin "1") (pinfunction "1_1") (pintype "passive"))
      (node (ref "U303") (pin "13") (pinfunction "OUTA_13") (pintype "passive"))
    )
    (net (code "125") (name "Net-(U303-OUTB)") (class "Default")
      (node (ref "C327") (pin "1") (pinfunction "1_1") (pintype "passive"))
      (node (ref "U303") (pin "12") (pinfunction "OUTB_12") (pintype "passive"))
    )
    (net (code "126") (name "Net-(U303-OUTC)") (class "Default")
      (node (ref "C329") (pin "1") (pinfunction "1_1") (pintype "passive"))
      (node (ref "U303") (pin "9") (pinfunction "OUTC_9") (pintype "passive"))
    )
    (net (code "127") (name "Net-(U303-OUTD)") (class "Default")
      (node (ref "C328") (pin "1") (pinfunction "1_1") (pintype "passive"))
      (node (ref "U303") (pin "8") (pinfunction "OUTD_8") (pintype "passive"))
    )
    (net (code "128") (name "Net-(U304-OUT)") (class "Default")
      (node (ref "R310") (pin "1") (pinfunction "1_1") (pintype "passive"))
      (node (ref "U304") (pin "7") (pinfunction "OUT_7") (pintype "passive"))
    )
    (net (code "129") (name "Net-(U305-OUTA)") (class "Default")
      (node (ref "U305") (pin "13") (pinfunction "OUTA_13") (pintype "passive"))
      (node (ref "U307") (pin "2") (pinfunction "INA_2") (pintype "passive"))
    )
    (net (code "130") (name "Net-(U306-OUTA)") (class "Default")
      (node (ref "U306") (pin "7") (pinfunction "OUTA_7") (pintype "passive"))
      (node (ref "U307") (pin "6") (pinfunction "VCC_6") (pintype "passive"))
    )
    (net (code "131") (name "VSUB_DC") (class "Default")
      (node (ref "C347") (pin "2") (pinfunction "2_2") (pintype "passive"))
      (node (ref "C351") (pin "2") (pinfunction "2_2") (pintype "passive"))
      (node (ref "D306") (pin "1") (pinfunction "1_1") (pintype "passive"))
    )
    (net (code "132") (name "unconnected-(U300-NC-Pad31)") (class "Default")
      (node (ref "U300") (pin "31") (pinfunction "NC_31") (pintype "passive+no_connect"))
    )
    (net (code "133") (name "unconnected-(U300-NC-Pad37)") (class "Default")
      (node (ref "U300") (pin "37") (pinfunction "NC_37") (pintype "passive+no_connect"))
    )
    (net (code "134") (name "unconnected-(U300-NC-Pad42)") (class "Default")
      (node (ref "U300") (pin "42") (pinfunction "NC_42") (pintype "passive+no_connect"))
    )
    (net (code "135") (name "unconnected-(U301-NC-Pad31)") (class "Default")
      (node (ref "U301") (pin "31") (pinfunction "NC_31") (pintype "passive+no_connect"))
    )
    (net (code "136") (name "unconnected-(U301-NC-Pad37)") (class "Default")
      (node (ref "U301") (pin "37") (pinfunction "NC_37") (pintype "passive+no_connect"))
    )
    (net (code "137") (name "unconnected-(U301-NC-Pad42)") (class "Default")
      (node (ref "U301") (pin "42") (pinfunction "NC_42") (pintype "passive+no_connect"))
    )
    (net (code "138") (name "unconnected-(U305-OUTC-Pad9)") (class "Default")
      (node (ref "U305") (pin "9") (pinfunction "OUTC_9") (pintype "passive+no_connect"))
    )
    (net (code "139") (name "unconnected-(U305-OUTD-Pad8)") (class "Default")
      (node (ref "U305") (pin "8") (pinfunction "OUTD_8") (pintype "passive+no_connect"))
    )
    (net (code "140") (name "unconnected-(U306-NC-Pad1)") (class "Default")
      (node (ref "U306") (pin "1") (pinfunction "NC_1") (pintype "passive+no_connect"))
    )
    (net (code "141") (name "unconnected-(U306-NC-Pad8)") (class "Default")
      (node (ref "U306") (pin "8") (pinfunction "NC_8") (pintype "passive+no_connect"))
    )
    (net (code "142") (name "unconnected-(U306-OUTB-Pad5)") (class "Default")
      (node (ref "U306") (pin "5") (pinfunction "OUTB_5") (pintype "passive+no_connect"))
    )
    (net (code "143") (name "unconnected-(U307-NC-Pad1)") (class "Default")
      (node (ref "U307") (pin "1") (pinfunction "NC_1") (pintype "passive+no_connect"))
    )
    (net (code "144") (name "unconnected-(U307-NC-Pad8)") (class "Default")
      (node (ref "U307") (pin "8") (pinfunction "NC_8") (pintype "passive+no_connect"))
    )
    (net (code "145") (name "unconnected-(U307-OUTB-Pad5)") (class "Default")
      (node (ref "U307") (pin "5") (pinfunction "OUTB_5") (pintype "passive+no_connect"))
    )
  )
)
